# Davi_APDS9960.net
KiCad netlist of a schematic drawn in EAGLE
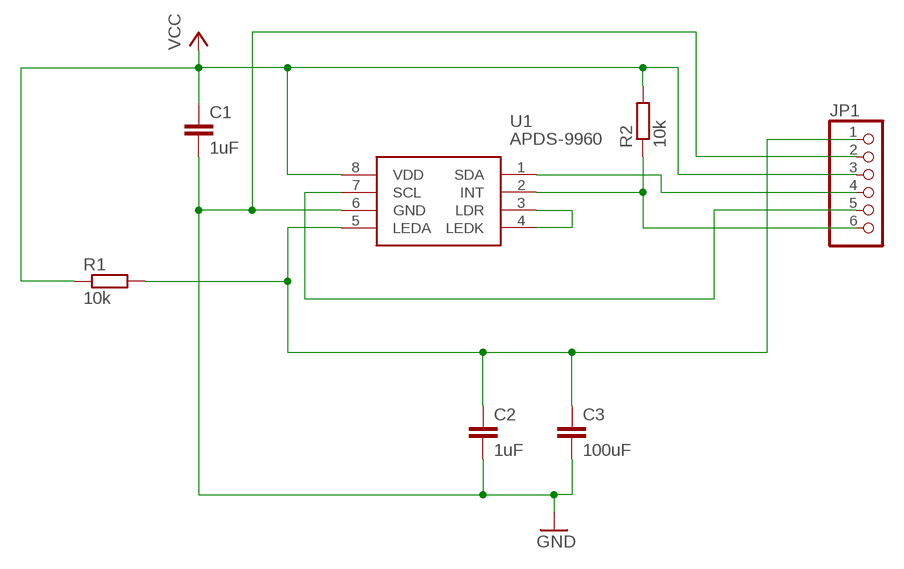
[diagram p0: schematic, sheet 1]

(export (version "E")
  (design (tool "Eeschema 10.0.6"))
  (components
    (comp (ref "C1")
      (value "1uF")
      (footprint "eagle-import:C025-025X050")
      (libsource (lib "eagle-import") (part "C-EU025-025X050"))
    )
    (comp (ref "C2")
      (value "1uF")
      (footprint "eagle-import:C025-025X050")
      (libsource (lib "eagle-import") (part "C-EU025-025X050"))
    )
    (comp (ref "C3")
      (value "100uF")
      (footprint "eagle-import:C025-025X050")
      (libsource (lib "eagle-import") (part "C-EU025-025X050"))
    )
    (comp (ref "JP1")
      (value "PINHD-1X6")
      (footprint "eagle-import:1X06")
      (libsource (lib "eagle-import") (part "PINHD-1X6"))
    )
    (comp (ref "R1")
      (value "10k")
      (footprint "eagle-import:0207_7")
      (libsource (lib "eagle-import") (part "R-EU_0207/7"))
    )
    (comp (ref "R2")
      (value "10k")
      (footprint "eagle-import:0207_7")
      (libsource (lib "eagle-import") (part "R-EU_0207/7"))
    )
    (comp (ref "U1")
      (value "APDS-9960")
      (footprint "eagle-import:APDS-9950")
      (fields (field (name "MOUSER_PART_NUMBER") "630-APDS-9960"))
      (libsource (lib "eagle-import") (part "APDS-9960"))
    )
  )
  (nets
    (net (code "1") (name "GND") (class "Default")
      (node (ref "C1") (pin "2") (pinfunction "2_2") (pintype "passive"))
      (node (ref "C2") (pin "2") (pinfunction "2_2") (pintype "passive"))
      (node (ref "C3") (pin "2") (pinfunction "2_2") (pintype "passive"))
      (node (ref "JP1") (pin "2") (pinfunction "2_2") (pintype "passive"))
      (node (ref "U1") (pin "6") (pinfunction "GND_6") (pintype "bidirectional"))
    )
    (net (code "2") (name "Net-(U1-INT)") (class "Default")
      (node (ref "JP1") (pin "6") (pinfunction "6_6") (pintype "passive"))
      (node (ref "R2") (pin "1") (pinfunction "1_1") (pintype "passive"))
      (node (ref "U1") (pin "2") (pinfunction "INT_2") (pintype "bidirectional"))
    )
    (net (code "3") (name "Net-(U1-LDR)") (class "Default")
      (node (ref "U1") (pin "3") (pinfunction "LDR_3") (pintype "bidirectional"))
      (node (ref "U1") (pin "4") (pinfunction "LEDK_4") (pintype "bidirectional"))
    )
    (net (code "4") (name "Net-(U1-LEDA)") (class "Default")
      (node (ref "C2") (pin "1") (pinfunction "1_1") (pintype "passive"))
      (node (ref "C3") (pin "1") (pinfunction "1_1") (pintype "passive"))
      (node (ref "JP1") (pin "1") (pinfunction "1_1") (pintype "passive"))
      (node (ref "R1") (pin "2") (pinfunction "2_2") (pintype "passive"))
      (node (ref "U1") (pin "5") (pinfunction "LEDA_5") (pintype "bidirectional"))
    )
    (net (code "5") (name "Net-(U1-SCL)") (class "Default")
      (node (ref "JP1") (pin "5") (pinfunction "5_5") (pintype "passive"))
      (node (ref "U1") (pin "7") (pinfunction "SCL_7") (pintype "bidirectional"))
    )
    (net (code "6") (name "Net-(U1-SDA)") (class "Default")
      (node (ref "JP1") (pin "4") (pinfunction "4_4") (pintype "passive"))
      (node (ref "U1") (pin "1") (pinfunction "SDA_1") (pintype "bidirectional"))
    )
    (net (code "7") (name "VCC") (class "Default")
      (node (ref "C1") (pin "1") (pinfunction "1_1") (pintype "passive"))
      (node (ref "JP1") (pin "3") (pinfunction "3_3") (pintype "passive"))
      (node (ref "R1") (pin "1") (pinfunction "1_1") (pintype "passive"))
      (node (ref "R2") (pin "2") (pinfunction "2_2") (pintype "passive"))
      (node (ref "U1") (pin "8") (pinfunction "VDD_8") (pintype "bidirectional"))
    )
  )
)
